# ft232.net
KiCad netlist of a schematic drawn in Altium Designer
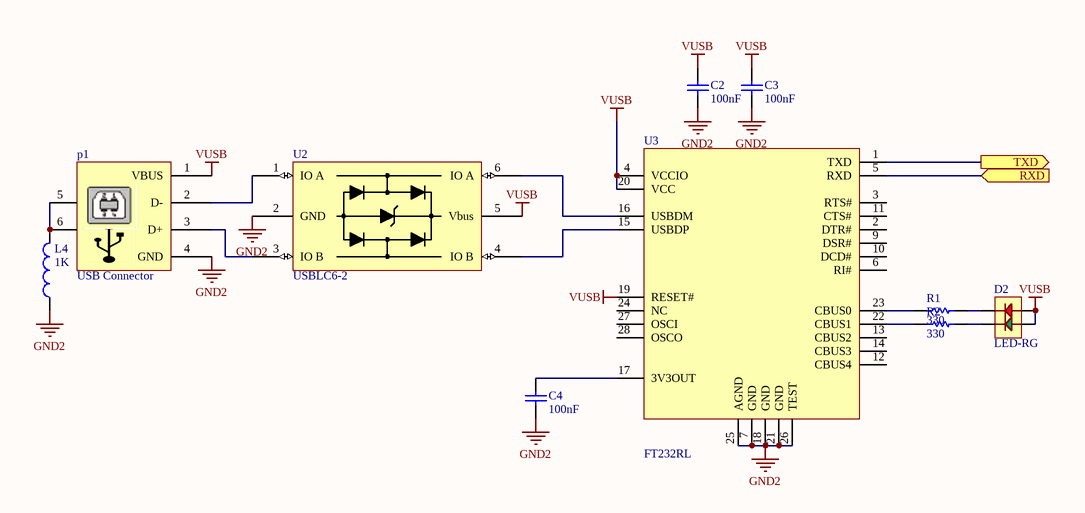
[diagram p0: ft232.SchDoc]

(export (version "E")
  (design (tool "Eeschema 10.0.6"))
  (components
    (comp (ref "C2")
      (value "100nF")
      (footprint "C805")
      (description "Capacitor")
      (fields (field (name "DESIGNER") "Parsa Malekpour"))
      (libsource (lib "ParsaLibrary") (part "Cap"))
    )
    (comp (ref "C3")
      (value "100nF")
      (footprint "C805")
      (description "Capacitor")
      (fields (field (name "DESIGNER") "Parsa Malekpour"))
      (libsource (lib "ParsaLibrary") (part "Cap"))
    )
    (comp (ref "C4")
      (value "100nF")
      (footprint "C805")
      (description "Capacitor")
      (fields (field (name "DESIGNER") "Parsa Malekpour"))
      (libsource (lib "ParsaLibrary") (part "Cap"))
    )
    (comp (ref "D2")
      (value "LED-RG")
      (footprint "LED-1210")
      (libsource (lib "ParsaLibrary") (part "LED-RG-4"))
    )
    (comp (ref "L4")
      (value "1K")
      (footprint "r805")
      (description "FERRITE BEAD")
      (fields (field (name "PUBLISHER") "Altium Limited"))
      (libsource (lib "ParsaLibrary") (part "Ferrite Bead"))
    )
    (comp (ref "p1")
      (value "USB Connector")
      (footprint "USB2-B-R")
      (description "USB Connector-B Type")
      (fields (field (name "DESIGNER") "Eng. Saeid Jorablo"))
      (libsource (lib "ParsaLibrary") (part "USB2-B"))
    )
    (comp (ref "R1")
      (value "330")
      (footprint "R0603")
      (description "Resistor")
      (fields (field (name "DESIGNER") "Parsa Malekpour"))
      (libsource (lib "ParsaLibrary") (part "Resistor"))
    )
    (comp (ref "R2")
      (value "330")
      (footprint "R0603")
      (description "Resistor")
      (fields (field (name "DESIGNER") "Parsa Malekpour"))
      (libsource (lib "ParsaLibrary") (part "Resistor"))
    )
    (comp (ref "U2")
      (value "USBLC6-2")
      (footprint "SOT-23-6")
      (description "Very low capacitance ESD protection")
      (libsource (lib "ParsaLibrary") (part "USBLC6-2"))
    )
    (comp (ref "U3")
      (value "FT232RL")
      (footprint "SSOP-28N")
      (libsource (lib "ParsaLibrary") (part "FT232RL"))
    )
  )
  (nets
    (net (code "1") (name "/RXD") (class "Default")
      (node (ref "U3") (pin "5") (pinfunction "RXD_5") (pintype "passive"))
    )
    (net (code "2") (name "/TXD") (class "Default")
      (node (ref "U3") (pin "1") (pinfunction "TXD_1") (pintype "passive"))
    )
    (net (code "3") (name "GND2") (class "Default")
      (node (ref "C2") (pin "1") (pinfunction "1_1") (pintype "passive"))
      (node (ref "C3") (pin "1") (pinfunction "1_1") (pintype "passive"))
      (node (ref "C4") (pin "1") (pinfunction "1_1") (pintype "passive"))
      (node (ref "L4") (pin "1") (pinfunction "1_1") (pintype "passive"))
      (node (ref "U2") (pin "2") (pinfunction "GND_2") (pintype "power_in"))
      (node (ref "U3") (pin "18") (pinfunction "GND_18") (pintype "passive"))
      (node (ref "U3") (pin "21") (pinfunction "GND_21") (pintype "passive"))
      (node (ref "U3") (pin "25") (pinfunction "AGND_25") (pintype "passive"))
      (node (ref "U3") (pin "26") (pinfunction "TEST_26") (pintype "passive"))
      (node (ref "U3") (pin "7") (pinfunction "GND_7") (pintype "passive"))
      (node (ref "p1") (pin "4") (pinfunction "GND_4") (pintype "power_in"))
    )
    (net (code "4") (name "Net-(D2-GRN-C)") (class "Default")
      (node (ref "D2") (pin "4") (pinfunction "GRN-C_4") (pintype "passive"))
      (node (ref "R2") (pin "2") (pinfunction "2_2") (pintype "passive"))
    )
    (net (code "5") (name "Net-(D2-RED-C)") (class "Default")
      (node (ref "D2") (pin "3") (pinfunction "RED-C_3") (pintype "passive"))
      (node (ref "R1") (pin "2") (pinfunction "2_2") (pintype "passive"))
    )
    (net (code "6") (name "Net-(L4-Pad2)") (class "Default")
      (node (ref "L4") (pin "2") (pinfunction "2_2") (pintype "passive"))
      (node (ref "p1") (pin "5") (pinfunction "5_5") (pintype "passive"))
      (node (ref "p1") (pin "6") (pinfunction "6_6") (pintype "passive"))
    )
    (net (code "7") (name "Net-(U3-3V3OUT)") (class "Default")
      (node (ref "C4") (pin "2") (pinfunction "2_2") (pintype "passive"))
      (node (ref "U3") (pin "17") (pinfunction "3V3OUT_17") (pintype "passive"))
    )
    (net (code "8") (name "Net-(U3-CBUS0)") (class "Default")
      (node (ref "R1") (pin "1") (pinfunction "1_1") (pintype "passive"))
      (node (ref "U3") (pin "23") (pinfunction "CBUS0_23") (pintype "passive"))
    )
    (net (code "9") (name "Net-(U3-CBUS1)") (class "Default")
      (node (ref "R2") (pin "1") (pinfunction "1_1") (pintype "passive"))
      (node (ref "U3") (pin "22") (pinfunction "CBUS1_22") (pintype "passive"))
    )
    (net (code "10") (name "Net-(U3-USBDM)") (class "Default")
      (node (ref "U2") (pin "6") (pinfunction "IO_A_6") (pintype "bidirectional"))
      (node (ref "U3") (pin "16") (pinfunction "USBDM_16") (pintype "passive"))
    )
    (net (code "11") (name "Net-(U3-USBDP)") (class "Default")
      (node (ref "U2") (pin "4") (pinfunction "IO_B_4") (pintype "bidirectional"))
      (node (ref "U3") (pin "15") (pinfunction "USBDP_15") (pintype "passive"))
    )
    (net (code "12") (name "Net-(p1-D+)") (class "Default")
      (node (ref "U2") (pin "3") (pinfunction "IO_B_3") (pintype "bidirectional"))
      (node (ref "p1") (pin "3") (pinfunction "D+_3") (pintype "passive"))
    )
    (net (code "13") (name "Net-(p1-D-)") (class "Default")
      (node (ref "U2") (pin "1") (pinfunction "IO_A_1") (pintype "bidirectional"))
      (node (ref "p1") (pin "2") (pinfunction "D-_2") (pintype "passive"))
    )
    (net (code "14") (name "VUSB") (class "Default")
      (node (ref "C2") (pin "2") (pinfunction "2_2") (pintype "passive"))
      (node (ref "C3") (pin "2") (pinfunction "2_2") (pintype "passive"))
      (node (ref "D2") (pin "1") (pinfunction "GRN-A_1") (pintype "passive"))
      (node (ref "D2") (pin "2") (pinfunction "RED-A_2") (pintype "passive"))
      (node (ref "U2") (pin "5") (pinfunction "Vbus_5") (pintype "power_in"))
      (node (ref "U3") (pin "19") (pinfunction "RESET#_19") (pintype "passive"))
      (node (ref "U3") (pin "20") (pinfunction "VCC_20") (pintype "passive"))
      (node (ref "U3") (pin "4") (pinfunction "VCCIO_4") (pintype "passive"))
      (node (ref "p1") (pin "1") (pinfunction "VBUS_1") (pintype "power_in"))
    )
    (net (code "15") (name "unconnected-(U3-CBUS2-Pad13)") (class "Default")
      (node (ref "U3") (pin "13") (pinfunction "CBUS2_13") (pintype "passive"))
    )
    (net (code "16") (name "unconnected-(U3-CBUS3-Pad14)") (class "Default")
      (node (ref "U3") (pin "14") (pinfunction "CBUS3_14") (pintype "passive"))
    )
    (net (code "17") (name "unconnected-(U3-CBUS4-Pad12)") (class "Default")
      (node (ref "U3") (pin "12") (pinfunction "CBUS4_12") (pintype "passive"))
    )
    (net (code "18") (name "unconnected-(U3-CTS#-Pad11)") (class "Default")
      (node (ref "U3") (pin "11") (pinfunction "CTS#_11") (pintype "passive"))
    )
    (net (code "19") (name "unconnected-(U3-DCD#-Pad10)") (class "Default")
      (node (ref "U3") (pin "10") (pinfunction "DCD#_10") (pintype "passive"))
    )
    (net (code "20") (name "unconnected-(U3-DSR#-Pad9)") (class "Default")
      (node (ref "U3") (pin "9") (pinfunction "DSR#_9") (pintype "passive"))
    )
    (net (code "21") (name "unconnected-(U3-DTR#-Pad2)") (class "Default")
      (node (ref "U3") (pin "2") (pinfunction "DTR#_2") (pintype "passive"))
    )
    (net (code "22") (name "unconnected-(U3-NC-Pad8)") (class "Default")
      (node (ref "U3") (pin "8") (pinfunction "NC_8") (pintype "passive"))
    )
    (net (code "23") (name "unconnected-(U3-NC-Pad24)") (class "Default")
      (node (ref "U3") (pin "24") (pinfunction "NC_24") (pintype "passive"))
    )
    (net (code "24") (name "unconnected-(U3-OSCI-Pad27)") (class "Default")
      (node (ref "U3") (pin "27") (pinfunction "OSCI_27") (pintype "passive"))
    )
    (net (code "25") (name "unconnected-(U3-OSCO-Pad28)") (class "Default")
      (node (ref "U3") (pin "28") (pinfunction "OSCO_28") (pintype "passive"))
    )
    (net (code "26") (name "unconnected-(U3-RI#-Pad6)") (class "Default")
      (node (ref "U3") (pin "6") (pinfunction "RI#_6") (pintype "passive"))
    )
    (net (code "27") (name "unconnected-(U3-RTS#-Pad3)") (class "Default")
      (node (ref "U3") (pin "3") (pinfunction "RTS#_3") (pintype "passive"))
    )
  )
)
